# vco_module.net
KiCad netlist of a schematic drawn in EAGLE
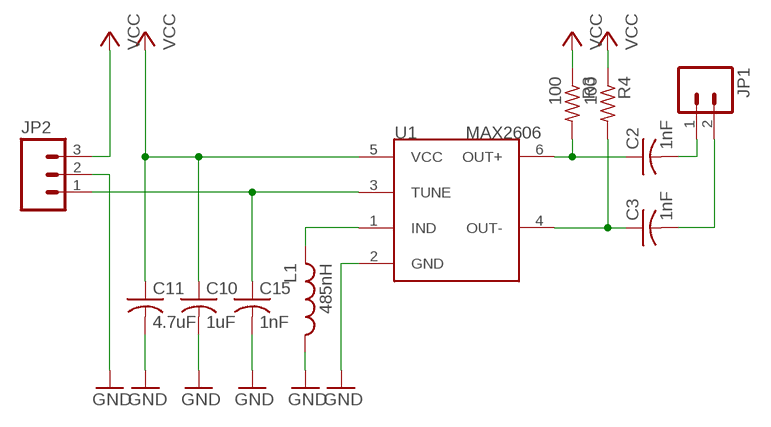
[diagram p0: schematic, sheet 1]

(export (version "E")
  (design (tool "Eeschema 10.0.6"))
  (components
    (comp (ref "C2")
      (value "1nF")
      (footprint "eagle-import:C050-025X075")
      (libsource (lib "eagle-import") (part "C-US050-025X075"))
    )
    (comp (ref "C3")
      (value "1nF")
      (footprint "eagle-import:C050-025X075")
      (libsource (lib "eagle-import") (part "C-US050-025X075"))
    )
    (comp (ref "C10")
      (value "1uF")
      (footprint "eagle-import:C050-025X075")
      (libsource (lib "eagle-import") (part "C-US050-025X075"))
    )
    (comp (ref "C11")
      (value "4.7uF")
      (footprint "eagle-import:C050-025X075")
      (libsource (lib "eagle-import") (part "C-US050-025X075"))
    )
    (comp (ref "C15")
      (value "1nF")
      (footprint "eagle-import:C050-025X075")
      (libsource (lib "eagle-import") (part "C-US050-025X075"))
    )
    (comp (ref "JP1")
      (value "M023.5MM")
      (footprint "eagle-import:SCREWTERMINAL-3.5MM-2")
      (libsource (lib "eagle-import") (part "M023.5MM"))
    )
    (comp (ref "JP2")
      (value "M03PTH")
      (footprint "eagle-import:1X03")
      (libsource (lib "eagle-import") (part "M03PTH"))
    )
    (comp (ref "L1")
      (value "485nH")
      (footprint "eagle-import:0204V")
      (libsource (lib "eagle-import") (part "L-US0204V"))
    )
    (comp (ref "R3")
      (value "100")
      (footprint "eagle-import:0207_10")
      (libsource (lib "eagle-import") (part "R-US_0207/10"))
    )
    (comp (ref "R4")
      (value "100")
      (footprint "eagle-import:0207_10")
      (libsource (lib "eagle-import") (part "R-US_0207/10"))
    )
    (comp (ref "U1")
      (value "MAX2606")
      (footprint "eagle-import:SOT23-6L")
      (libsource (lib "eagle-import") (part "MAX2606"))
    )
  )
  (nets
    (net (code "1") (name "GND") (class "Default")
      (node (ref "C10") (pin "2") (pinfunction "2_2") (pintype "passive"))
      (node (ref "C11") (pin "2") (pinfunction "2_2") (pintype "passive"))
      (node (ref "C15") (pin "2") (pinfunction "2_2") (pintype "passive"))
      (node (ref "JP2") (pin "2") (pinfunction "2_2") (pintype "passive"))
      (node (ref "L1") (pin "1") (pinfunction "1_1") (pintype "passive"))
      (node (ref "U1") (pin "2") (pinfunction "GND_2") (pintype "bidirectional"))
    )
    (net (code "2") (name "Net-(C2-Pad2)") (class "Default")
      (node (ref "C2") (pin "2") (pinfunction "2_2") (pintype "passive"))
      (node (ref "JP1") (pin "1") (pinfunction "1_1") (pintype "passive"))
    )
    (net (code "3") (name "Net-(C3-Pad2)") (class "Default")
      (node (ref "C3") (pin "2") (pinfunction "2_2") (pintype "passive"))
      (node (ref "JP1") (pin "2") (pinfunction "2_2") (pintype "passive"))
    )
    (net (code "4") (name "Net-(U1-IND)") (class "Default")
      (node (ref "L1") (pin "2") (pinfunction "2_2") (pintype "passive"))
      (node (ref "U1") (pin "1") (pinfunction "IND_1") (pintype "bidirectional"))
    )
    (net (code "5") (name "Net-(U1-OUT+)") (class "Default")
      (node (ref "C2") (pin "1") (pinfunction "1_1") (pintype "passive"))
      (node (ref "R3") (pin "2") (pinfunction "2_2") (pintype "passive"))
      (node (ref "U1") (pin "6") (pinfunction "OUT+_6") (pintype "bidirectional"))
    )
    (net (code "6") (name "Net-(U1-OUT-)") (class "Default")
      (node (ref "C3") (pin "1") (pinfunction "1_1") (pintype "passive"))
      (node (ref "R4") (pin "2") (pinfunction "2_2") (pintype "passive"))
      (node (ref "U1") (pin "4") (pinfunction "OUT-_4") (pintype "bidirectional"))
    )
    (net (code "7") (name "Net-(U1-TUNE)") (class "Default")
      (node (ref "C15") (pin "1") (pinfunction "1_1") (pintype "passive"))
      (node (ref "JP2") (pin "1") (pinfunction "1_1") (pintype "passive"))
      (node (ref "U1") (pin "3") (pinfunction "TUNE_3") (pintype "bidirectional"))
    )
    (net (code "8") (name "VCC") (class "Default")
      (node (ref "C10") (pin "1") (pinfunction "1_1") (pintype "passive"))
      (node (ref "C11") (pin "1") (pinfunction "1_1") (pintype "passive"))
      (node (ref "JP2") (pin "3") (pinfunction "3_3") (pintype "passive"))
      (node (ref "R3") (pin "1") (pinfunction "1_1") (pintype "passive"))
      (node (ref "R4") (pin "1") (pinfunction "1_1") (pintype "passive"))
      (node (ref "U1") (pin "5") (pinfunction "VCC_5") (pintype "bidirectional"))
    )
  )
)
